# schematic.net
KiCad netlist of a schematic drawn in EAGLE
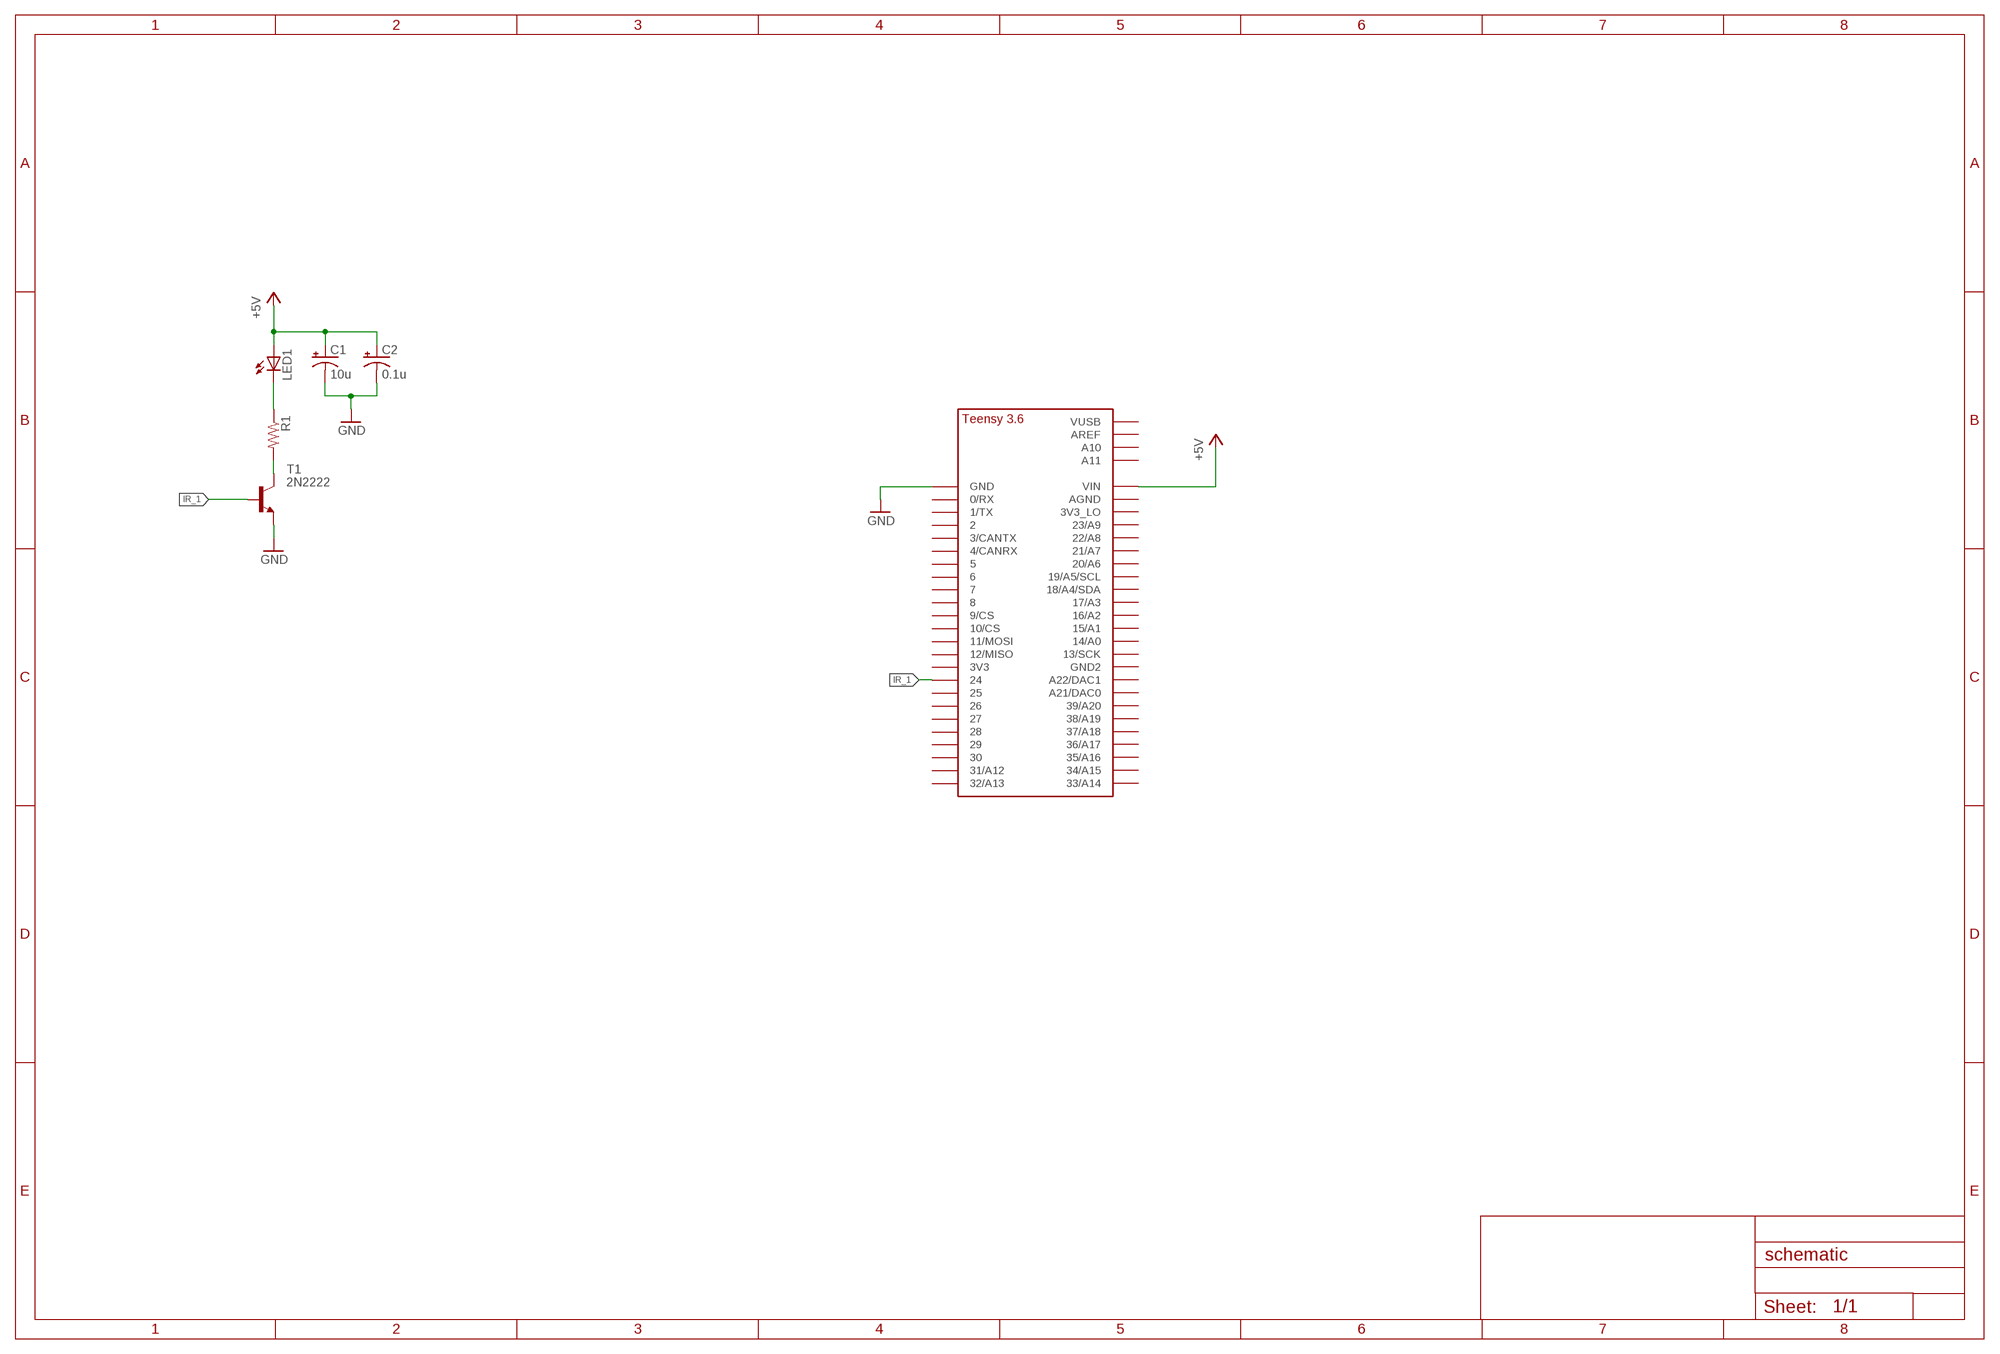
[diagram p0: schematic, sheet 1]

(export (version "E")
  (design (tool "Eeschema 10.0.6"))
  (components
    (comp (ref "C1")
      (value "10u")
      (footprint "eagle-import:E3,5-8")
      (libsource (lib "eagle-import") (part "CPOL-USE3.5-8"))
    )
    (comp (ref "C2")
      (value "0.1u")
      (footprint "eagle-import:E1,8-4")
      (libsource (lib "eagle-import") (part "CPOL-USE1.8-4"))
    )
    (comp (ref "LED1")
      (value "LED5MM")
      (footprint "eagle-import:LED5MM")
      (libsource (lib "eagle-import") (part "LED5MM"))
    )
    (comp (ref "R1")
      (value "R-US_0204/7")
      (footprint "eagle-import:0204_7")
      (libsource (lib "eagle-import") (part "R-US_0204/7"))
    )
    (comp (ref "T1")
      (value "2N2222")
      (footprint "eagle-import:TO92-EBC-OVAL")
      (libsource (lib "eagle-import") (part "2N2222"))
    )
    (comp (ref "U$1")
      (value "TEENSY_3.5/3.6_BASIC")
      (footprint "eagle-import:TEENSY_3.5_3.6_BASIC")
      (libsource (lib "eagle-import") (part "TEENSY_3.5/3.6_BASIC"))
    )
  )
  (nets
    (net (code "1") (name "+5V") (class "Default")
      (node (ref "C1") (pin "+") (pinfunction "+_+") (pintype "passive"))
      (node (ref "C2") (pin "+") (pinfunction "+_+") (pintype "passive"))
      (node (ref "LED1") (pin "A") (pinfunction "A_A") (pintype "passive"))
      (node (ref "U$1") (pin "VIN") (pinfunction "VIN_VIN") (pintype "bidirectional"))
    )
    (net (code "2") (name "GND") (class "Default")
      (node (ref "C1") (pin "-") (pinfunction "-_-") (pintype "passive"))
      (node (ref "C2") (pin "-") (pinfunction "-_-") (pintype "passive"))
      (node (ref "T1") (pin "E") (pinfunction "E_E") (pintype "passive"))
      (node (ref "U$1") (pin "GND") (pinfunction "GND_GND") (pintype "bidirectional"))
    )
    (net (code "3") (name "IR_1") (class "Default")
      (node (ref "T1") (pin "B") (pinfunction "B_B") (pintype "passive"))
      (node (ref "U$1") (pin "24") (pinfunction "24_24") (pintype "bidirectional"))
    )
    (net (code "4") (name "Net-(LED1-C)") (class "Default")
      (node (ref "LED1") (pin "K") (pinfunction "C_K") (pintype "passive"))
      (node (ref "R1") (pin "1") (pinfunction "1_1") (pintype "passive"))
    )
    (net (code "5") (name "Net-(R1-Pad2)") (class "Default")
      (node (ref "R1") (pin "2") (pinfunction "2_2") (pintype "passive"))
      (node (ref "T1") (pin "C") (pinfunction "C_C") (pintype "passive"))
    )
    (net (code "6") (name "unconnected-(U$1-A21{slash}DAC0-Pad21{slash}DAC0)") (class "Default")
      (node (ref "U$1") (pin "21/DAC0") (pinfunction "A21/DAC0_21/DAC0") (pintype "bidirectional"))
    )
    (net (code "7") (name "unconnected-(U$1-Pad0{slash}RX)") (class "Default")
      (node (ref "U$1") (pin "0/RX") (pinfunction "0/RX_0/RX") (pintype "bidirectional"))
    )
    (net (code "8") (name "unconnected-(U$1-Pad1{slash}TX)") (class "Default")
      (node (ref "U$1") (pin "1/TX") (pinfunction "1/TX_1/TX") (pintype "bidirectional"))
    )
    (net (code "9") (name "unconnected-(U$1-Pad2)") (class "Default")
      (node (ref "U$1") (pin "2") (pinfunction "2_2") (pintype "bidirectional"))
    )
    (net (code "10") (name "unconnected-(U$1-Pad3V3)") (class "Default")
      (node (ref "U$1") (pin "3V3") (pinfunction "3V3_3V3") (pintype "bidirectional"))
    )
    (net (code "11") (name "unconnected-(U$1-Pad3V3_LO)") (class "Default")
      (node (ref "U$1") (pin "3V3_LO") (pinfunction "3V3_LO_3V3_LO") (pintype "bidirectional"))
    )
    (net (code "12") (name "unconnected-(U$1-Pad3{slash}CANTX)") (class "Default")
      (node (ref "U$1") (pin "3/CANTX") (pinfunction "3/CANTX_3/CANTX") (pintype "bidirectional"))
    )
    (net (code "13") (name "unconnected-(U$1-Pad4{slash}CANRX)") (class "Default")
      (node (ref "U$1") (pin "4/CANRX") (pinfunction "4/CANRX_4/CANRX") (pintype "bidirectional"))
    )
    (net (code "14") (name "unconnected-(U$1-Pad5)") (class "Default")
      (node (ref "U$1") (pin "5") (pinfunction "5_5") (pintype "bidirectional"))
    )
    (net (code "15") (name "unconnected-(U$1-Pad6)") (class "Default")
      (node (ref "U$1") (pin "6") (pinfunction "6_6") (pintype "bidirectional"))
    )
    (net (code "16") (name "unconnected-(U$1-Pad7)") (class "Default")
      (node (ref "U$1") (pin "7") (pinfunction "7_7") (pintype "bidirectional"))
    )
    (net (code "17") (name "unconnected-(U$1-Pad8)") (class "Default")
      (node (ref "U$1") (pin "8") (pinfunction "8_8") (pintype "bidirectional"))
    )
    (net (code "18") (name "unconnected-(U$1-Pad9{slash}CS)") (class "Default")
      (node (ref "U$1") (pin "9/CS") (pinfunction "9/CS_9/CS") (pintype "bidirectional"))
    )
    (net (code "19") (name "unconnected-(U$1-Pad10{slash}CS)") (class "Default")
      (node (ref "U$1") (pin "10/CS") (pinfunction "10/CS_10/CS") (pintype "bidirectional"))
    )
    (net (code "20") (name "unconnected-(U$1-Pad11{slash}MOSI)") (class "Default")
      (node (ref "U$1") (pin "11/MOSI") (pinfunction "11/MOSI_11/MOSI") (pintype "bidirectional"))
    )
    (net (code "21") (name "unconnected-(U$1-Pad12{slash}MISO)") (class "Default")
      (node (ref "U$1") (pin "12/MISO") (pinfunction "12/MISO_12/MISO") (pintype "bidirectional"))
    )
    (net (code "22") (name "unconnected-(U$1-Pad13{slash}SCK)") (class "Default")
      (node (ref "U$1") (pin "13/SCK") (pinfunction "13/SCK_13/SCK") (pintype "bidirectional"))
    )
    (net (code "23") (name "unconnected-(U$1-Pad14{slash}A0)") (class "Default")
      (node (ref "U$1") (pin "14/A0") (pinfunction "14/A0_14/A0") (pintype "bidirectional"))
    )
    (net (code "24") (name "unconnected-(U$1-Pad15{slash}A1)") (class "Default")
      (node (ref "U$1") (pin "15/A1") (pinfunction "15/A1_15/A1") (pintype "bidirectional"))
    )
    (net (code "25") (name "unconnected-(U$1-Pad16{slash}A2)") (class "Default")
      (node (ref "U$1") (pin "16/A2") (pinfunction "16/A2_16/A2") (pintype "bidirectional"))
    )
    (net (code "26") (name "unconnected-(U$1-Pad17{slash}A3)") (class "Default")
      (node (ref "U$1") (pin "17/A3") (pinfunction "17/A3_17/A3") (pintype "bidirectional"))
    )
    (net (code "27") (name "unconnected-(U$1-Pad18{slash}A4{slash}SDA)") (class "Default")
      (node (ref "U$1") (pin "18/A4/SDA") (pinfunction "18/A4/SDA_18/A4/SDA") (pintype "bidirectional"))
    )
    (net (code "28") (name "unconnected-(U$1-Pad19{slash}A5{slash}SCL)") (class "Default")
      (node (ref "U$1") (pin "19/A5/SCL") (pinfunction "19/A5/SCL_19/A5/SCL") (pintype "bidirectional"))
    )
    (net (code "29") (name "unconnected-(U$1-Pad20{slash}A6)") (class "Default")
      (node (ref "U$1") (pin "20/A6") (pinfunction "20/A6_20/A6") (pintype "bidirectional"))
    )
    (net (code "30") (name "unconnected-(U$1-Pad21{slash}A7)") (class "Default")
      (node (ref "U$1") (pin "21/A7") (pinfunction "21/A7_21/A7") (pintype "bidirectional"))
    )
    (net (code "31") (name "unconnected-(U$1-Pad22{slash}A8)") (class "Default")
      (node (ref "U$1") (pin "22/A8") (pinfunction "22/A8_22/A8") (pintype "bidirectional"))
    )
    (net (code "32") (name "unconnected-(U$1-Pad23{slash}A9)") (class "Default")
      (node (ref "U$1") (pin "23/A9") (pinfunction "23/A9_23/A9") (pintype "bidirectional"))
    )
    (net (code "33") (name "unconnected-(U$1-Pad25)") (class "Default")
      (node (ref "U$1") (pin "25") (pinfunction "25_25") (pintype "bidirectional"))
    )
    (net (code "34") (name "unconnected-(U$1-Pad26)") (class "Default")
      (node (ref "U$1") (pin "26") (pinfunction "26_26") (pintype "bidirectional"))
    )
    (net (code "35") (name "unconnected-(U$1-Pad27)") (class "Default")
      (node (ref "U$1") (pin "27") (pinfunction "27_27") (pintype "bidirectional"))
    )
    (net (code "36") (name "unconnected-(U$1-Pad28)") (class "Default")
      (node (ref "U$1") (pin "28") (pinfunction "28_28") (pintype "bidirectional"))
    )
    (net (code "37") (name "unconnected-(U$1-Pad29)") (class "Default")
      (node (ref "U$1") (pin "29") (pinfunction "29_29") (pintype "bidirectional"))
    )
    (net (code "38") (name "unconnected-(U$1-Pad30)") (class "Default")
      (node (ref "U$1") (pin "30") (pinfunction "30_30") (pintype "bidirectional"))
    )
    (net (code "39") (name "unconnected-(U$1-Pad31{slash}A12)") (class "Default")
      (node (ref "U$1") (pin "31/A12") (pinfunction "31/A12_31/A12") (pintype "bidirectional"))
    )
    (net (code "40") (name "unconnected-(U$1-Pad32{slash}A13)") (class "Default")
      (node (ref "U$1") (pin "32/A13") (pinfunction "32/A13_32/A13") (pintype "bidirectional"))
    )
    (net (code "41") (name "unconnected-(U$1-Pad33{slash}A14)") (class "Default")
      (node (ref "U$1") (pin "33/A14") (pinfunction "33/A14_33/A14") (pintype "bidirectional"))
    )
    (net (code "42") (name "unconnected-(U$1-Pad34{slash}A15)") (class "Default")
      (node (ref "U$1") (pin "34/A15") (pinfunction "34/A15_34/A15") (pintype "bidirectional"))
    )
    (net (code "43") (name "unconnected-(U$1-Pad35{slash}A16)") (class "Default")
      (node (ref "U$1") (pin "35/A16") (pinfunction "35/A16_35/A16") (pintype "bidirectional"))
    )
    (net (code "44") (name "unconnected-(U$1-Pad36{slash}A17)") (class "Default")
      (node (ref "U$1") (pin "36/A17") (pinfunction "36/A17_36/A17") (pintype "bidirectional"))
    )
    (net (code "45") (name "unconnected-(U$1-Pad37{slash}A18)") (class "Default")
      (node (ref "U$1") (pin "37/A18") (pinfunction "37/A18_37/A18") (pintype "bidirectional"))
    )
    (net (code "46") (name "unconnected-(U$1-Pad38{slash}A19)") (class "Default")
      (node (ref "U$1") (pin "38/A19") (pinfunction "38/A19_38/A19") (pintype "bidirectional"))
    )
    (net (code "47") (name "unconnected-(U$1-Pad39{slash}A20)") (class "Default")
      (node (ref "U$1") (pin "39/A20") (pinfunction "39/A20_39/A20") (pintype "bidirectional"))
    )
    (net (code "48") (name "unconnected-(U$1-PadA10)") (class "Default")
      (node (ref "U$1") (pin "A10") (pinfunction "A10_A10") (pintype "bidirectional"))
    )
    (net (code "49") (name "unconnected-(U$1-PadA11)") (class "Default")
      (node (ref "U$1") (pin "A11") (pinfunction "A11_A11") (pintype "bidirectional"))
    )
    (net (code "50") (name "unconnected-(U$1-PadA22{slash}DAC1)") (class "Default")
      (node (ref "U$1") (pin "A22/DAC1") (pinfunction "A22/DAC1_A22/DAC1") (pintype "bidirectional"))
    )
    (net (code "51") (name "unconnected-(U$1-PadAGND)") (class "Default")
      (node (ref "U$1") (pin "AGND") (pinfunction "AGND_AGND") (pintype "bidirectional"))
    )
    (net (code "52") (name "unconnected-(U$1-PadAREF)") (class "Default")
      (node (ref "U$1") (pin "AREF") (pinfunction "AREF_AREF") (pintype "bidirectional"))
    )
    (net (code "53") (name "unconnected-(U$1-PadGND2)") (class "Default")
      (node (ref "U$1") (pin "GND2") (pinfunction "GND2_GND2") (pintype "bidirectional"))
    )
    (net (code "54") (name "unconnected-(U$1-PadVUSB)") (class "Default")
      (node (ref "U$1") (pin "VUSB") (pinfunction "VUSB_VUSB") (pintype "bidirectional"))
    )
  )
)
